# LPS22HB_pcb.net
KiCad netlist of a schematic drawn in EAGLE
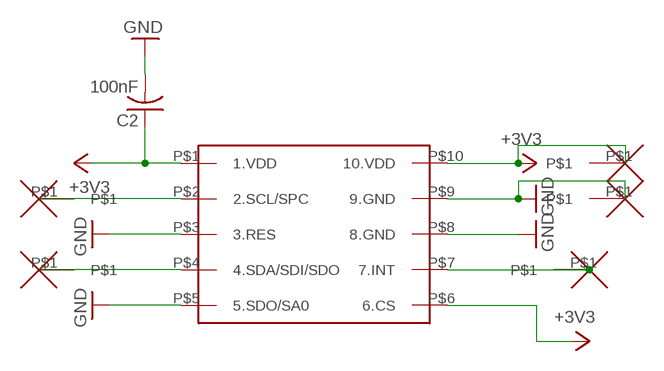
[diagram p0: schematic, sheet 1]

(export (version "E")
  (design (tool "Eeschema 10.0.6"))
  (components
    (comp (ref "C2")
      (value "100nF")
      (footprint "eagle-import:C0402")
      (libsource (lib "eagle-import") (part "C-USC0402"))
    )
    (comp (ref "U$1")
      (value "LPS22HB_HLGA")
      (footprint "eagle-import:LPS22HB_HLGA")
      (libsource (lib "eagle-import") (part "LPS22HB_HLGA"))
    )
    (comp (ref "U$2")
      (value "WIREPAD_0,8/0,45")
      (footprint "eagle-import:WIREPAD_0,8_0,45")
      (libsource (lib "eagle-import") (part "WIREPAD_0,8/0,45"))
    )
    (comp (ref "U$3")
      (value "WIREPAD_0,8/0,45")
      (footprint "eagle-import:WIREPAD_0,8_0,45")
      (libsource (lib "eagle-import") (part "WIREPAD_0,8/0,45"))
    )
    (comp (ref "U$6")
      (value "WIREPAD_0,8/0,45")
      (footprint "eagle-import:WIREPAD_0,8_0,45")
      (libsource (lib "eagle-import") (part "WIREPAD_0,8/0,45"))
    )
    (comp (ref "U$7")
      (value "WIREPAD_0,8/0,45")
      (footprint "eagle-import:WIREPAD_0,8_0,45")
      (libsource (lib "eagle-import") (part "WIREPAD_0,8/0,45"))
    )
    (comp (ref "U$8")
      (value "WIREPAD_0,8/0,45")
      (footprint "eagle-import:WIREPAD_0,8_0,45")
      (libsource (lib "eagle-import") (part "WIREPAD_0,8/0,45"))
    )
  )
  (nets
    (net (code "1") (name "+3V3") (class "Default")
      (node (ref "C2") (pin "1") (pinfunction "1_1") (pintype "passive"))
      (node (ref "U$1") (pin "P$1") (pinfunction "1.VDD_P$1") (pintype "bidirectional"))
      (node (ref "U$1") (pin "P$10") (pinfunction "10.VDD_P$10") (pintype "bidirectional"))
      (node (ref "U$1") (pin "P$6") (pinfunction "6.CS_P$6") (pintype "bidirectional"))
      (node (ref "U$8") (pin "P$1") (pinfunction "P$1_P$1") (pintype "bidirectional"))
    )
    (net (code "2") (name "GND") (class "Default")
      (node (ref "C2") (pin "2") (pinfunction "2_2") (pintype "passive"))
      (node (ref "U$1") (pin "P$3") (pinfunction "3.RES_P$3") (pintype "bidirectional"))
      (node (ref "U$1") (pin "P$5") (pinfunction "5.SDO/SA0_P$5") (pintype "bidirectional"))
      (node (ref "U$1") (pin "P$8") (pinfunction "8.GND_P$8") (pintype "bidirectional"))
      (node (ref "U$1") (pin "P$9") (pinfunction "9.GND_P$9") (pintype "bidirectional"))
      (node (ref "U$7") (pin "P$1") (pinfunction "P$1_P$1") (pintype "bidirectional"))
    )
    (net (code "3") (name "Net-(U$1-2.SCL{slash}SPC)") (class "Default")
      (node (ref "U$1") (pin "P$2") (pinfunction "2.SCL/SPC_P$2") (pintype "bidirectional"))
      (node (ref "U$2") (pin "P$1") (pinfunction "P$1_P$1") (pintype "bidirectional"))
    )
    (net (code "4") (name "Net-(U$1-4.SDA{slash}SDI{slash}SDO)") (class "Default")
      (node (ref "U$1") (pin "P$4") (pinfunction "4.SDA/SDI/SDO_P$4") (pintype "bidirectional"))
      (node (ref "U$3") (pin "P$1") (pinfunction "P$1_P$1") (pintype "bidirectional"))
    )
    (net (code "5") (name "Net-(U$1-7.INT)") (class "Default")
      (node (ref "U$1") (pin "P$7") (pinfunction "7.INT_P$7") (pintype "bidirectional"))
      (node (ref "U$6") (pin "P$1") (pinfunction "P$1_P$1") (pintype "bidirectional"))
    )
  )
)
